# M621A.net
KiCad netlist of a schematic drawn in EAGLE
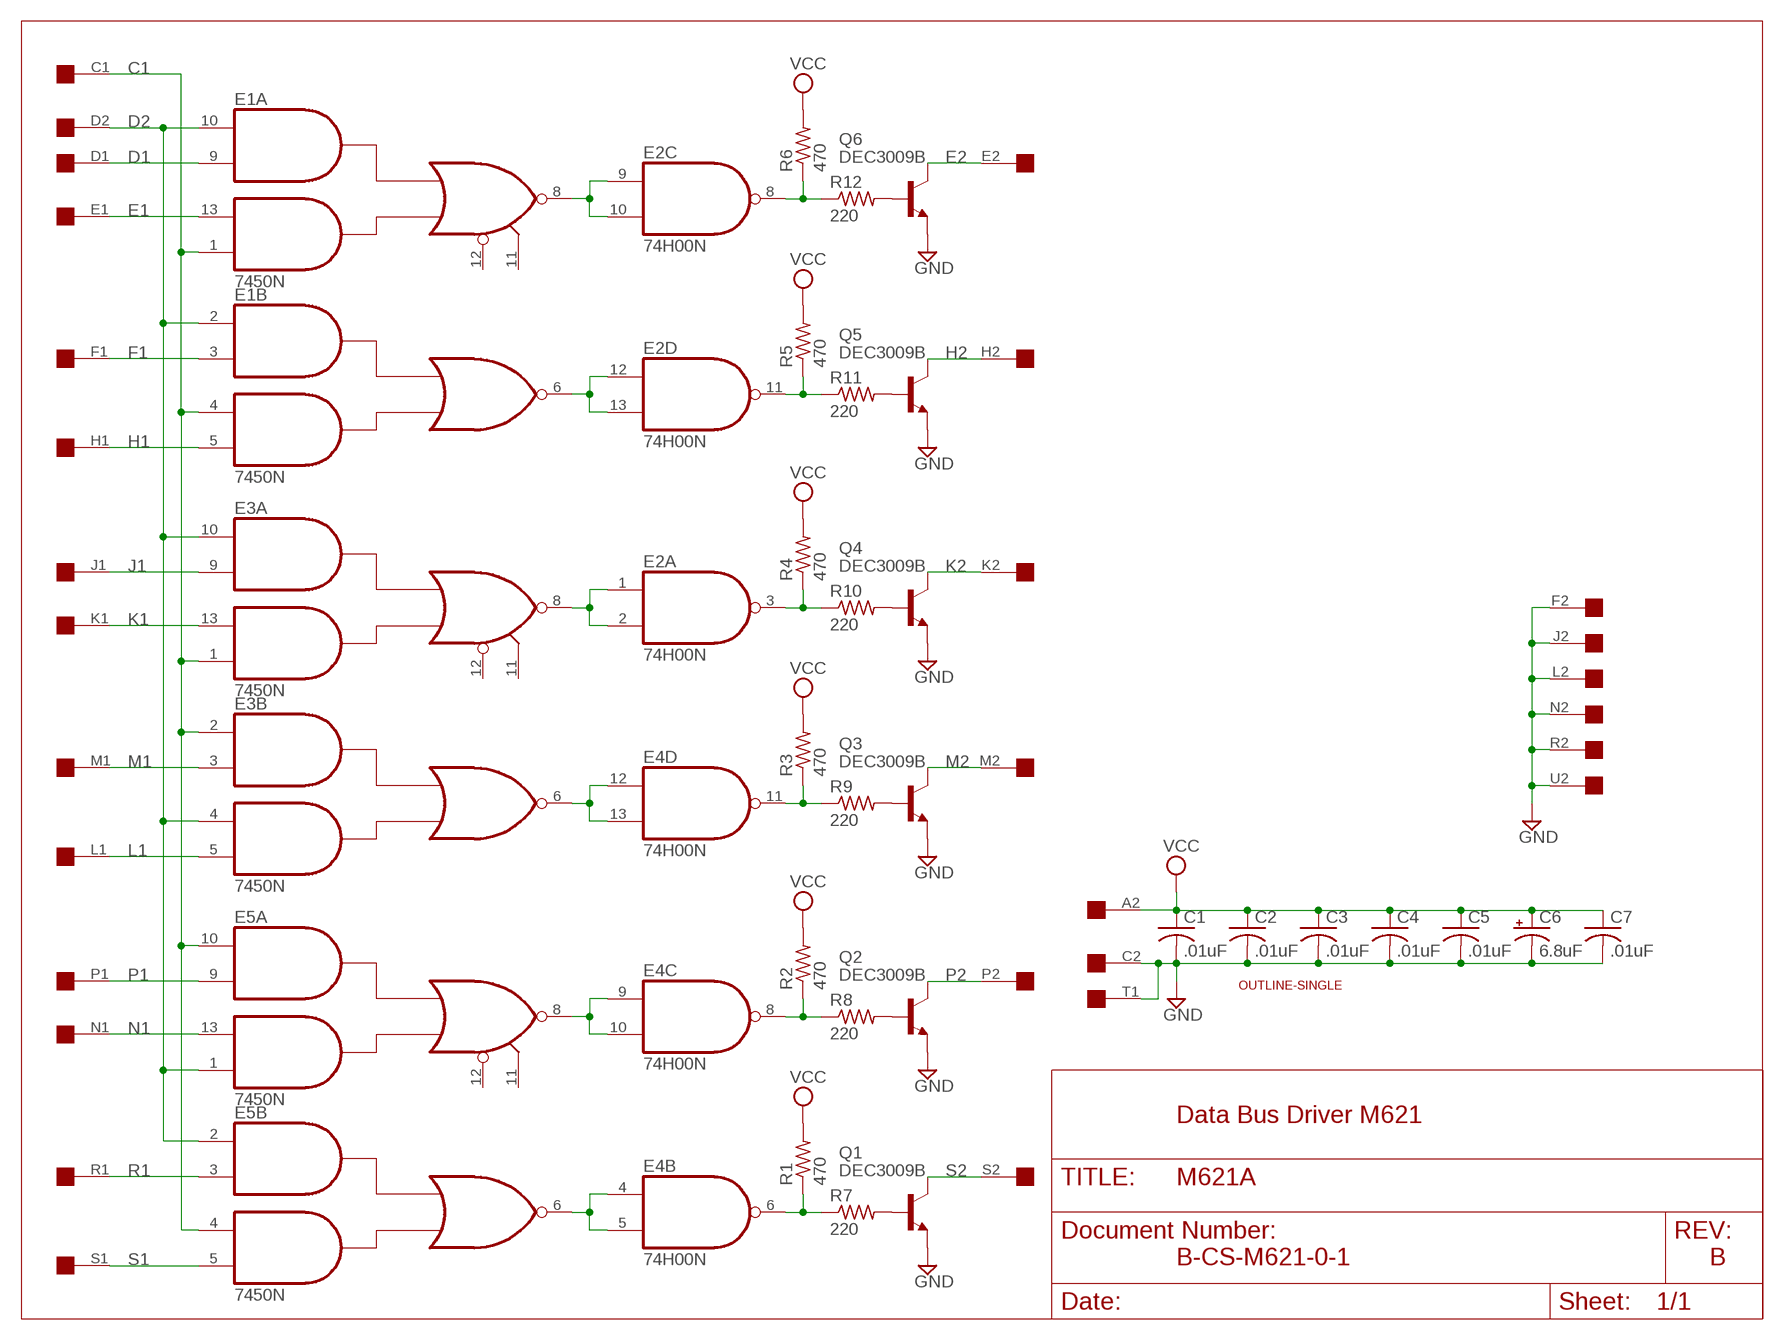
[diagram p0: schematic, sheet 1]

(export (version "E")
  (design (tool "Eeschema 10.0.6"))
  (components
    (comp (ref "C1")
      (value ".01uF")
      (footprint "eagle-import:C063-025X075")
      (libsource (lib "eagle-import") (part "C-US"))
    )
    (comp (ref "C2")
      (value ".01uF")
      (footprint "eagle-import:C063-025X075")
      (libsource (lib "eagle-import") (part "C-US"))
    )
    (comp (ref "C3")
      (value ".01uF")
      (footprint "eagle-import:C063-025X075")
      (libsource (lib "eagle-import") (part "C-US"))
    )
    (comp (ref "C4")
      (value ".01uF")
      (footprint "eagle-import:C063-025X075")
      (libsource (lib "eagle-import") (part "C-US"))
    )
    (comp (ref "C5")
      (value ".01uF")
      (footprint "eagle-import:C063-025X075")
      (libsource (lib "eagle-import") (part "C-US"))
    )
    (comp (ref "C6")
      (value "6.8uF")
      (footprint "eagle-import:E15-5")
      (libsource (lib "eagle-import") (part "CPOL-USE15-5AXIAL"))
    )
    (comp (ref "C7")
      (value ".01uF")
      (footprint "eagle-import:C063-025X075")
      (libsource (lib "eagle-import") (part "C-US"))
    )
    (comp (ref "E1")
      (value "7450N")
      (footprint "eagle-import:DIL14")
      (libsource (lib "eagle-import") (part "7450N"))
    )
    (comp (ref "E2")
      (value "74H00N")
      (footprint "eagle-import:DIL14")
      (libsource (lib "eagle-import") (part "7400NS"))
    )
    (comp (ref "E3")
      (value "7450N")
      (footprint "eagle-import:DIL14")
      (libsource (lib "eagle-import") (part "7450N"))
    )
    (comp (ref "E4")
      (value "74H00N")
      (footprint "eagle-import:DIL14")
      (libsource (lib "eagle-import") (part "7400NS"))
    )
    (comp (ref "E5")
      (value "7450N")
      (footprint "eagle-import:DIL14")
      (libsource (lib "eagle-import") (part "7450N"))
    )
    (comp (ref "Q1")
      (value "DEC3009B")
      (footprint "eagle-import:TO5")
      (libsource (lib "eagle-import") (part "-NPN-TO5"))
    )
    (comp (ref "Q2")
      (value "DEC3009B")
      (footprint "eagle-import:TO5")
      (libsource (lib "eagle-import") (part "-NPN-TO5"))
    )
    (comp (ref "Q3")
      (value "DEC3009B")
      (footprint "eagle-import:TO5")
      (libsource (lib "eagle-import") (part "-NPN-TO5"))
    )
    (comp (ref "Q4")
      (value "DEC3009B")
      (footprint "eagle-import:TO5")
      (libsource (lib "eagle-import") (part "-NPN-TO5"))
    )
    (comp (ref "Q5")
      (value "DEC3009B")
      (footprint "eagle-import:TO5")
      (libsource (lib "eagle-import") (part "-NPN-TO5"))
    )
    (comp (ref "Q6")
      (value "DEC3009B")
      (footprint "eagle-import:TO5")
      (libsource (lib "eagle-import") (part "-NPN-TO5"))
    )
    (comp (ref "R1")
      (value "470")
      (footprint "eagle-import:0207_10")
      (libsource (lib "eagle-import") (part "R-US_0207/10"))
    )
    (comp (ref "R2")
      (value "470")
      (footprint "eagle-import:0207_10")
      (libsource (lib "eagle-import") (part "R-US_0207/10"))
    )
    (comp (ref "R3")
      (value "470")
      (footprint "eagle-import:0207_10")
      (libsource (lib "eagle-import") (part "R-US_0207/10"))
    )
    (comp (ref "R4")
      (value "470")
      (footprint "eagle-import:0207_10")
      (libsource (lib "eagle-import") (part "R-US_0207/10"))
    )
    (comp (ref "R5")
      (value "470")
      (footprint "eagle-import:0207_10")
      (libsource (lib "eagle-import") (part "R-US_0207/10"))
    )
    (comp (ref "R6")
      (value "470")
      (footprint "eagle-import:0207_10")
      (libsource (lib "eagle-import") (part "R-US_0207/10"))
    )
    (comp (ref "R7")
      (value "220")
      (footprint "eagle-import:0207_10")
      (libsource (lib "eagle-import") (part "R-US_0207/10"))
    )
    (comp (ref "R8")
      (value "220")
      (footprint "eagle-import:0207_10")
      (libsource (lib "eagle-import") (part "R-US_0207/10"))
    )
    (comp (ref "R9")
      (value "220")
      (footprint "eagle-import:0207_10")
      (libsource (lib "eagle-import") (part "R-US_0207/10"))
    )
    (comp (ref "R10")
      (value "220")
      (footprint "eagle-import:0207_10")
      (libsource (lib "eagle-import") (part "R-US_0207/10"))
    )
    (comp (ref "R11")
      (value "220")
      (footprint "eagle-import:0207_10")
      (libsource (lib "eagle-import") (part "R-US_0207/10"))
    )
    (comp (ref "R12")
      (value "220")
      (footprint "eagle-import:0207_10")
      (libsource (lib "eagle-import") (part "R-US_0207/10"))
    )
    (comp (ref "U$1")
      (value "OUTLINE-SINGLE")
      (footprint "eagle-import:SINGLE")
      (libsource (lib "eagle-import") (part "OUTLINE-SINGLE"))
    )
    (comp (ref "U$2")
      (value "edge")
      (footprint "eagle-import:EDGE-CON2")
      (libsource (lib "eagle-import") (part "SINGLE"))
    )
  )
  (nets
    (net (code "1") (name "/C1") (class "Default")
      (node (ref "E1") (pin "1") (pinfunction "I4_1") (pintype "input"))
      (node (ref "E1") (pin "4") (pinfunction "I3_4") (pintype "input"))
      (node (ref "E3") (pin "1") (pinfunction "I4_1") (pintype "input"))
      (node (ref "E3") (pin "2") (pinfunction "I1_2") (pintype "input"))
      (node (ref "E5") (pin "10") (pinfunction "I1_10") (pintype "input"))
      (node (ref "E5") (pin "4") (pinfunction "I3_4") (pintype "input"))
      (node (ref "U$2") (pin "C1") (pinfunction "1_C1") (pintype "bidirectional"))
    )
    (net (code "2") (name "/D1") (class "Default")
      (node (ref "E1") (pin "9") (pinfunction "I2_9") (pintype "input"))
      (node (ref "U$2") (pin "D1") (pinfunction "1_D1") (pintype "bidirectional"))
    )
    (net (code "3") (name "/D2") (class "Default")
      (node (ref "E1") (pin "10") (pinfunction "I1_10") (pintype "input"))
      (node (ref "E1") (pin "2") (pinfunction "I1_2") (pintype "input"))
      (node (ref "E3") (pin "10") (pinfunction "I1_10") (pintype "input"))
      (node (ref "E3") (pin "4") (pinfunction "I3_4") (pintype "input"))
      (node (ref "E5") (pin "1") (pinfunction "I4_1") (pintype "input"))
      (node (ref "E5") (pin "2") (pinfunction "I1_2") (pintype "input"))
      (node (ref "U$2") (pin "D2") (pinfunction "1_D2") (pintype "bidirectional"))
    )
    (net (code "4") (name "/E1") (class "Default")
      (node (ref "E1") (pin "13") (pinfunction "I3_13") (pintype "input"))
      (node (ref "U$2") (pin "E1") (pinfunction "1_E1") (pintype "bidirectional"))
    )
    (net (code "5") (name "/E2") (class "Default")
      (node (ref "Q6") (pin "3") (pinfunction "C_3") (pintype "passive"))
      (node (ref "U$2") (pin "E2") (pinfunction "1_E2") (pintype "bidirectional"))
    )
    (net (code "6") (name "/F1") (class "Default")
      (node (ref "E1") (pin "3") (pinfunction "I2_3") (pintype "input"))
      (node (ref "U$2") (pin "F1") (pinfunction "1_F1") (pintype "bidirectional"))
    )
    (net (code "7") (name "/H1") (class "Default")
      (node (ref "E1") (pin "5") (pinfunction "I4_5") (pintype "input"))
      (node (ref "U$2") (pin "H1") (pinfunction "1_H1") (pintype "bidirectional"))
    )
    (net (code "8") (name "/H2") (class "Default")
      (node (ref "Q5") (pin "3") (pinfunction "C_3") (pintype "passive"))
      (node (ref "U$2") (pin "H2") (pinfunction "1_H2") (pintype "bidirectional"))
    )
    (net (code "9") (name "/J1") (class "Default")
      (node (ref "E3") (pin "9") (pinfunction "I2_9") (pintype "input"))
      (node (ref "U$2") (pin "J1") (pinfunction "1_J1") (pintype "bidirectional"))
    )
    (net (code "10") (name "/K1") (class "Default")
      (node (ref "E3") (pin "13") (pinfunction "I3_13") (pintype "input"))
      (node (ref "U$2") (pin "K1") (pinfunction "1_K1") (pintype "bidirectional"))
    )
    (net (code "11") (name "/K2") (class "Default")
      (node (ref "Q4") (pin "3") (pinfunction "C_3") (pintype "passive"))
      (node (ref "U$2") (pin "K2") (pinfunction "1_K2") (pintype "bidirectional"))
    )
    (net (code "12") (name "/L1") (class "Default")
      (node (ref "E3") (pin "5") (pinfunction "I4_5") (pintype "input"))
      (node (ref "U$2") (pin "L1") (pinfunction "1_L1") (pintype "bidirectional"))
    )
    (net (code "13") (name "/M1") (class "Default")
      (node (ref "E3") (pin "3") (pinfunction "I2_3") (pintype "input"))
      (node (ref "U$2") (pin "M1") (pinfunction "1_M1") (pintype "bidirectional"))
    )
    (net (code "14") (name "/M2") (class "Default")
      (node (ref "Q3") (pin "3") (pinfunction "C_3") (pintype "passive"))
      (node (ref "U$2") (pin "M2") (pinfunction "1_M2") (pintype "bidirectional"))
    )
    (net (code "15") (name "/N1") (class "Default")
      (node (ref "E5") (pin "13") (pinfunction "I3_13") (pintype "input"))
      (node (ref "U$2") (pin "N1") (pinfunction "1_N1") (pintype "bidirectional"))
    )
    (net (code "16") (name "/P1") (class "Default")
      (node (ref "E5") (pin "9") (pinfunction "I2_9") (pintype "input"))
      (node (ref "U$2") (pin "P1") (pinfunction "1_P1") (pintype "bidirectional"))
    )
    (net (code "17") (name "/P2") (class "Default")
      (node (ref "Q2") (pin "3") (pinfunction "C_3") (pintype "passive"))
      (node (ref "U$2") (pin "P2") (pinfunction "1_P2") (pintype "bidirectional"))
    )
    (net (code "18") (name "/R1") (class "Default")
      (node (ref "E5") (pin "3") (pinfunction "I2_3") (pintype "input"))
      (node (ref "U$2") (pin "R1") (pinfunction "1_R1") (pintype "bidirectional"))
    )
    (net (code "19") (name "/S1") (class "Default")
      (node (ref "E5") (pin "5") (pinfunction "I4_5") (pintype "input"))
      (node (ref "U$2") (pin "S1") (pinfunction "1_S1") (pintype "bidirectional"))
    )
    (net (code "20") (name "/S2") (class "Default")
      (node (ref "Q1") (pin "3") (pinfunction "C_3") (pintype "passive"))
      (node (ref "U$2") (pin "S2") (pinfunction "1_S2") (pintype "bidirectional"))
    )
    (net (code "21") (name "GND") (class "Default")
      (node (ref "C1") (pin "2") (pinfunction "2_2") (pintype "passive"))
      (node (ref "C2") (pin "2") (pinfunction "2_2") (pintype "passive"))
      (node (ref "C3") (pin "2") (pinfunction "2_2") (pintype "passive"))
      (node (ref "C4") (pin "2") (pinfunction "2_2") (pintype "passive"))
      (node (ref "C5") (pin "2") (pinfunction "2_2") (pintype "passive"))
      (node (ref "C6") (pin "-") (pinfunction "-_-") (pintype "passive"))
      (node (ref "C7") (pin "2") (pinfunction "2_2") (pintype "passive"))
      (node (ref "Q1") (pin "1") (pinfunction "E_1") (pintype "passive"))
      (node (ref "Q2") (pin "1") (pinfunction "E_1") (pintype "passive"))
      (node (ref "Q3") (pin "1") (pinfunction "E_1") (pintype "passive"))
      (node (ref "Q4") (pin "1") (pinfunction "E_1") (pintype "passive"))
      (node (ref "Q5") (pin "1") (pinfunction "E_1") (pintype "passive"))
      (node (ref "Q6") (pin "1") (pinfunction "E_1") (pintype "passive"))
      (node (ref "U$2") (pin "C2") (pinfunction "1_C2") (pintype "bidirectional"))
      (node (ref "U$2") (pin "F2") (pinfunction "1_F2") (pintype "bidirectional"))
      (node (ref "U$2") (pin "J2") (pinfunction "1_J2") (pintype "bidirectional"))
      (node (ref "U$2") (pin "L2") (pinfunction "1_L2") (pintype "bidirectional"))
      (node (ref "U$2") (pin "N2") (pinfunction "1_N2") (pintype "bidirectional"))
      (node (ref "U$2") (pin "R2") (pinfunction "1_R2") (pintype "bidirectional"))
      (node (ref "U$2") (pin "T1") (pinfunction "1_T1") (pintype "bidirectional"))
      (node (ref "U$2") (pin "U2") (pinfunction "1_U2") (pintype "bidirectional"))
    )
    (net (code "22") (name "Net-(E1A-O)") (class "Default")
      (node (ref "E1") (pin "8") (pinfunction "O_8") (pintype "output"))
      (node (ref "E2") (pin "10") (pinfunction "I1_10") (pintype "input"))
      (node (ref "E2") (pin "9") (pinfunction "I0_9") (pintype "input"))
    )
    (net (code "23") (name "Net-(E1B-O)") (class "Default")
      (node (ref "E1") (pin "6") (pinfunction "O_6") (pintype "output"))
      (node (ref "E2") (pin "12") (pinfunction "I0_12") (pintype "input"))
      (node (ref "E2") (pin "13") (pinfunction "I1_13") (pintype "input"))
    )
    (net (code "24") (name "Net-(E2A-I0)") (class "Default")
      (node (ref "E2") (pin "1") (pinfunction "I0_1") (pintype "input"))
      (node (ref "E2") (pin "2") (pinfunction "I1_2") (pintype "input"))
      (node (ref "E3") (pin "8") (pinfunction "O_8") (pintype "output"))
    )
    (net (code "25") (name "Net-(E2A-O)") (class "Default")
      (node (ref "E2") (pin "3") (pinfunction "O_3") (pintype "output"))
      (node (ref "R10") (pin "1") (pinfunction "1_1") (pintype "passive"))
      (node (ref "R4") (pin "1") (pinfunction "1_1") (pintype "passive"))
    )
    (net (code "26") (name "Net-(E2C-O)") (class "Default")
      (node (ref "E2") (pin "8") (pinfunction "O_8") (pintype "output"))
      (node (ref "R12") (pin "1") (pinfunction "1_1") (pintype "passive"))
      (node (ref "R6") (pin "1") (pinfunction "1_1") (pintype "passive"))
    )
    (net (code "27") (name "Net-(E2D-O)") (class "Default")
      (node (ref "E2") (pin "11") (pinfunction "O_11") (pintype "output"))
      (node (ref "R11") (pin "1") (pinfunction "1_1") (pintype "passive"))
      (node (ref "R5") (pin "1") (pinfunction "1_1") (pintype "passive"))
    )
    (net (code "28") (name "Net-(E3B-O)") (class "Default")
      (node (ref "E3") (pin "6") (pinfunction "O_6") (pintype "output"))
      (node (ref "E4") (pin "12") (pinfunction "I0_12") (pintype "input"))
      (node (ref "E4") (pin "13") (pinfunction "I1_13") (pintype "input"))
    )
    (net (code "29") (name "Net-(E4B-I0)") (class "Default")
      (node (ref "E4") (pin "4") (pinfunction "I0_4") (pintype "input"))
      (node (ref "E4") (pin "5") (pinfunction "I1_5") (pintype "input"))
      (node (ref "E5") (pin "6") (pinfunction "O_6") (pintype "output"))
    )
    (net (code "30") (name "Net-(E4B-O)") (class "Default")
      (node (ref "E4") (pin "6") (pinfunction "O_6") (pintype "output"))
      (node (ref "R1") (pin "1") (pinfunction "1_1") (pintype "passive"))
      (node (ref "R7") (pin "1") (pinfunction "1_1") (pintype "passive"))
    )
    (net (code "31") (name "Net-(E4C-I0)") (class "Default")
      (node (ref "E4") (pin "10") (pinfunction "I1_10") (pintype "input"))
      (node (ref "E4") (pin "9") (pinfunction "I0_9") (pintype "input"))
      (node (ref "E5") (pin "8") (pinfunction "O_8") (pintype "output"))
    )
    (net (code "32") (name "Net-(E4C-O)") (class "Default")
      (node (ref "E4") (pin "8") (pinfunction "O_8") (pintype "output"))
      (node (ref "R2") (pin "1") (pinfunction "1_1") (pintype "passive"))
      (node (ref "R8") (pin "1") (pinfunction "1_1") (pintype "passive"))
    )
    (net (code "33") (name "Net-(E4D-O)") (class "Default")
      (node (ref "E4") (pin "11") (pinfunction "O_11") (pintype "output"))
      (node (ref "R3") (pin "1") (pinfunction "1_1") (pintype "passive"))
      (node (ref "R9") (pin "1") (pinfunction "1_1") (pintype "passive"))
    )
    (net (code "34") (name "Net-(Q1-B)") (class "Default")
      (node (ref "Q1") (pin "2") (pinfunction "B_2") (pintype "passive"))
      (node (ref "R7") (pin "2") (pinfunction "2_2") (pintype "passive"))
    )
    (net (code "35") (name "Net-(Q2-B)") (class "Default")
      (node (ref "Q2") (pin "2") (pinfunction "B_2") (pintype "passive"))
      (node (ref "R8") (pin "2") (pinfunction "2_2") (pintype "passive"))
    )
    (net (code "36") (name "Net-(Q3-B)") (class "Default")
      (node (ref "Q3") (pin "2") (pinfunction "B_2") (pintype "passive"))
      (node (ref "R9") (pin "2") (pinfunction "2_2") (pintype "passive"))
    )
    (net (code "37") (name "Net-(Q4-B)") (class "Default")
      (node (ref "Q4") (pin "2") (pinfunction "B_2") (pintype "passive"))
      (node (ref "R10") (pin "2") (pinfunction "2_2") (pintype "passive"))
    )
    (net (code "38") (name "Net-(Q5-B)") (class "Default")
      (node (ref "Q5") (pin "2") (pinfunction "B_2") (pintype "passive"))
      (node (ref "R11") (pin "2") (pinfunction "2_2") (pintype "passive"))
    )
    (net (code "39") (name "Net-(Q6-B)") (class "Default")
      (node (ref "Q6") (pin "2") (pinfunction "B_2") (pintype "passive"))
      (node (ref "R12") (pin "2") (pinfunction "2_2") (pintype "passive"))
    )
    (net (code "40") (name "VCC") (class "Default")
      (node (ref "C1") (pin "1") (pinfunction "1_1") (pintype "passive"))
      (node (ref "C2") (pin "1") (pinfunction "1_1") (pintype "passive"))
      (node (ref "C3") (pin "1") (pinfunction "1_1") (pintype "passive"))
      (node (ref "C4") (pin "1") (pinfunction "1_1") (pintype "passive"))
      (node (ref "C5") (pin "1") (pinfunction "1_1") (pintype "passive"))
      (node (ref "C6") (pin "+") (pinfunction "+_+") (pintype "passive"))
      (node (ref "C7") (pin "1") (pinfunction "1_1") (pintype "passive"))
      (node (ref "R1") (pin "2") (pinfunction "2_2") (pintype "passive"))
      (node (ref "R2") (pin "2") (pinfunction "2_2") (pintype "passive"))
      (node (ref "R3") (pin "2") (pinfunction "2_2") (pintype "passive"))
      (node (ref "R4") (pin "2") (pinfunction "2_2") (pintype "passive"))
      (node (ref "R5") (pin "2") (pinfunction "2_2") (pintype "passive"))
      (node (ref "R6") (pin "2") (pinfunction "2_2") (pintype "passive"))
      (node (ref "U$2") (pin "A2") (pinfunction "1_A2") (pintype "bidirectional"))
    )
    (net (code "41") (name "unconnected-(E1A-I5-Pad12)") (class "Default")
      (node (ref "E1") (pin "12") (pinfunction "I5_12") (pintype "passive"))
    )
    (net (code "42") (name "unconnected-(E1A-I6-Pad11)") (class "Default")
      (node (ref "E1") (pin "11") (pinfunction "I6_11") (pintype "passive"))
    )
    (net (code "43") (name "unconnected-(E3A-I5-Pad12)") (class "Default")
      (node (ref "E3") (pin "12") (pinfunction "I5_12") (pintype "passive"))
    )
    (net (code "44") (name "unconnected-(E3A-I6-Pad11)") (class "Default")
      (node (ref "E3") (pin "11") (pinfunction "I6_11") (pintype "passive"))
    )
    (net (code "45") (name "unconnected-(E5A-I5-Pad12)") (class "Default")
      (node (ref "E5") (pin "12") (pinfunction "I5_12") (pintype "passive"))
    )
    (net (code "46") (name "unconnected-(E5A-I6-Pad11)") (class "Default")
      (node (ref "E5") (pin "11") (pinfunction "I6_11") (pintype "passive"))
    )
  )
)
